# Memory-SD_UHS_II.net
KiCad netlist of a schematic drawn in Altium Designer
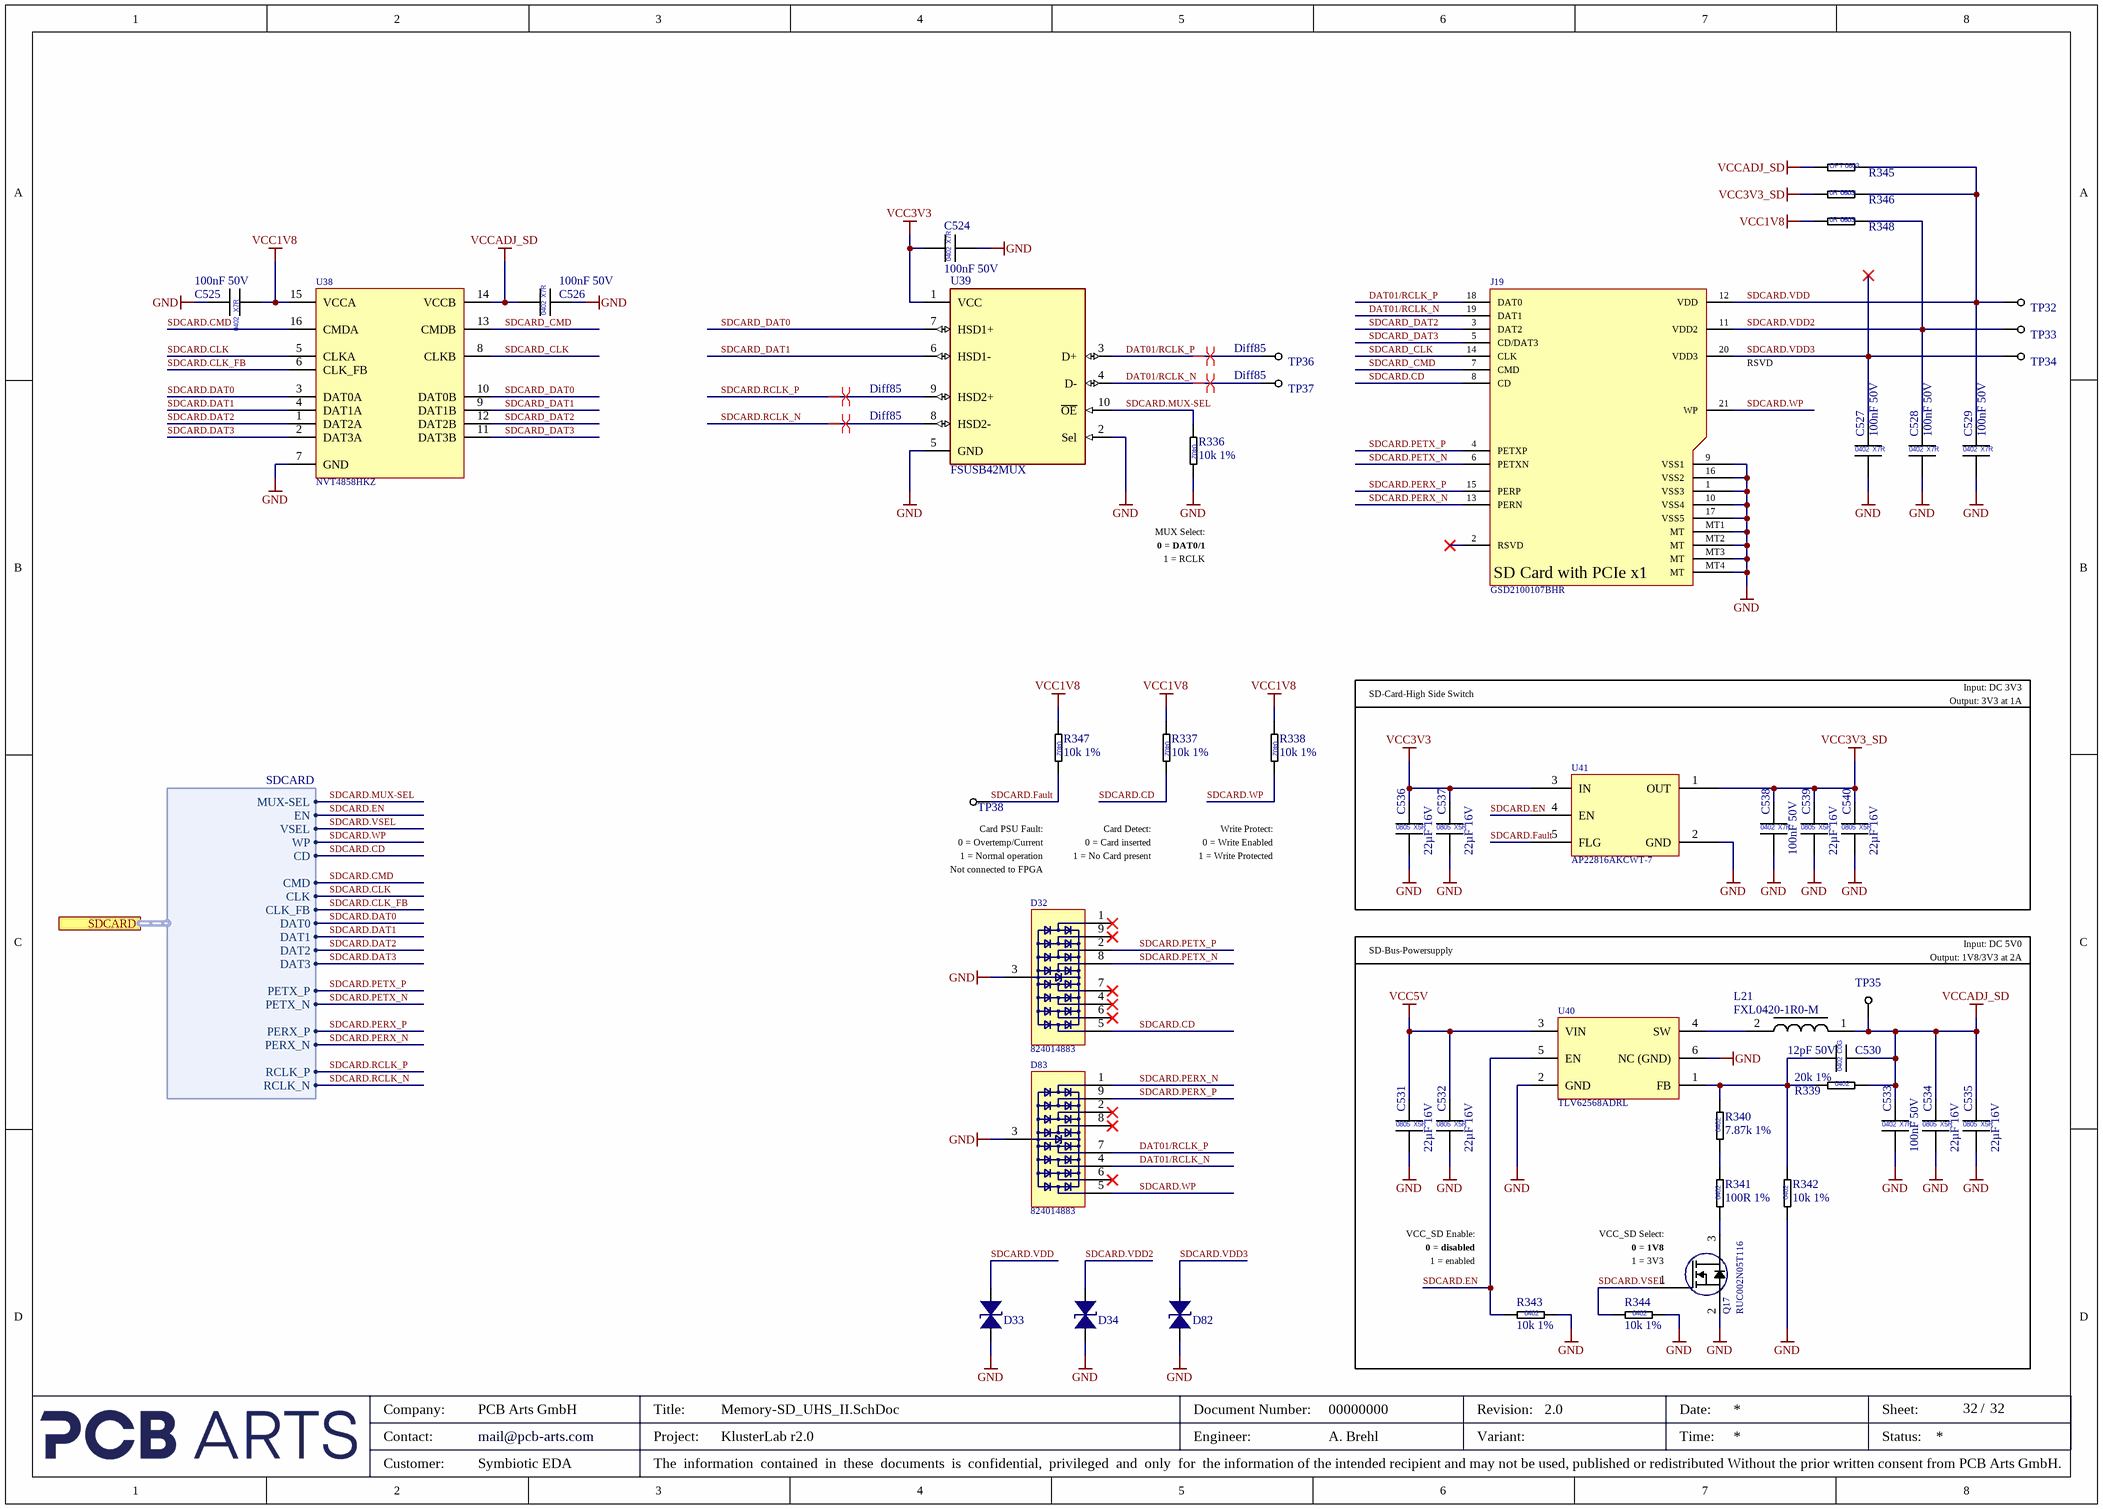
[diagram p0: Memory-SD_UHS_II.SchDoc]

(export (version "E")
  (design (tool "Eeschema 10.0.6"))
  (components
    (comp (ref "C524")
      (value "100nF 50V")
      (footprint "Cap:CAP_0402_L")
      (description "Multilayer Ceramic Capacitors MLCC - SMD/SMT 0402 50VDC")
      (libsource (lib "") (part "CAP_0402_100nF_50V_1"))
    )
    (comp (ref "C525")
      (value "100nF 50V")
      (footprint "Cap:CAP_0402_L")
      (description "Multilayer Ceramic Capacitors MLCC - SMD/SMT 0402 50VDC")
      (libsource (lib "Cap") (part "CAP_0402_100nF_50V"))
    )
    (comp (ref "C526")
      (value "100nF 50V")
      (footprint "Cap:CAP_0402_L")
      (description "Multilayer Ceramic Capacitors MLCC - SMD/SMT 0402 50VDC")
      (libsource (lib "") (part "CAP_0402_100nF_50V_1"))
    )
    (comp (ref "C527")
      (value "100nF 50V")
      (footprint "Cap:CAP_0402_L")
      (description "Multilayer Ceramic Capacitors MLCC - SMD/SMT 0402 50VDC")
      (libsource (lib "Cap") (part "CAP_0402_100nF_50V"))
    )
    (comp (ref "C528")
      (value "100nF 50V")
      (footprint "Cap:CAP_0402_L")
      (description "Multilayer Ceramic Capacitors MLCC - SMD/SMT 0402 50VDC")
      (libsource (lib "Cap") (part "CAP_0402_100nF_50V"))
    )
    (comp (ref "C529")
      (value "100nF 50V")
      (footprint "Cap:CAP_0402_L")
      (description "Multilayer Ceramic Capacitors MLCC - SMD/SMT 0402 50VDC")
      (libsource (lib "Cap") (part "CAP_0402_100nF_50V"))
    )
    (comp (ref "C530")
      (value "12pF 50V")
      (footprint "Cap:CAP_0402_L")
      (description "Multilayer Ceramic Capacitors MLCC - SMD/SMT 0402 50VDC")
      (libsource (lib "Cap") (part "CAP_0402_12pF_50V"))
    )
    (comp (ref "C531")
      (value "22µF 16V")
      (footprint "Cap:CAP_0805")
      (description "Multilayer Ceramic Capacitors MLCC - SMD/SMT 0805 16VDC")
      (libsource (lib "Cap") (part "CAP_0805_22µF_16V"))
    )
    (comp (ref "C532")
      (value "22µF 16V")
      (footprint "Cap:CAP_0805")
      (description "Multilayer Ceramic Capacitors MLCC - SMD/SMT 0805 16VDC")
      (libsource (lib "Cap") (part "CAP_0805_22µF_16V"))
    )
    (comp (ref "C533")
      (value "100nF 50V")
      (footprint "Cap:CAP_0402_L")
      (description "Multilayer Ceramic Capacitors MLCC - SMD/SMT 0402 50VDC")
      (libsource (lib "Cap") (part "CAP_0402_100nF_50V"))
    )
    (comp (ref "C534")
      (value "22µF 16V")
      (footprint "Cap:CAP_0805")
      (description "Multilayer Ceramic Capacitors MLCC - SMD/SMT 0805 16VDC")
      (libsource (lib "Cap") (part "CAP_0805_22µF_16V"))
    )
    (comp (ref "C535")
      (value "22µF 16V")
      (footprint "Cap:CAP_0805")
      (description "Multilayer Ceramic Capacitors MLCC - SMD/SMT 0805 16VDC")
      (libsource (lib "Cap") (part "CAP_0805_22µF_16V"))
    )
    (comp (ref "C536")
      (value "22µF 16V")
      (footprint "Cap:CAP_0805")
      (description "Multilayer Ceramic Capacitors MLCC - SMD/SMT 0805 16VDC")
      (libsource (lib "Cap") (part "CAP_0805_22µF_16V"))
    )
    (comp (ref "C537")
      (value "22µF 16V")
      (footprint "Cap:CAP_0805")
      (description "Multilayer Ceramic Capacitors MLCC - SMD/SMT 0805 16VDC")
      (libsource (lib "Cap") (part "CAP_0805_22µF_16V"))
    )
    (comp (ref "C538")
      (value "100nF 50V")
      (footprint "Cap:CAP_0402_L")
      (description "Multilayer Ceramic Capacitors MLCC - SMD/SMT 0402 50VDC")
      (libsource (lib "Cap") (part "CAP_0402_100nF_50V"))
    )
    (comp (ref "C539")
      (value "22µF 16V")
      (footprint "Cap:CAP_0805")
      (description "Multilayer Ceramic Capacitors MLCC - SMD/SMT 0805 16VDC")
      (libsource (lib "Cap") (part "CAP_0805_22µF_16V"))
    )
    (comp (ref "C540")
      (value "22µF 16V")
      (footprint "Cap:CAP_0805")
      (description "Multilayer Ceramic Capacitors MLCC - SMD/SMT 0805 16VDC")
      (libsource (lib "Cap") (part "CAP_0805_22µF_16V"))
    )
    (comp (ref "D32")
      (value "824014883")
      (footprint "WE-TVS-DFN3810-9L")
      (description "ESD Suppressors / TVS Diodes WE-TVS Diode Array 3.3V 0.5pF 8Channel")
      (libsource (lib "Protec") (part "824014883_ESD-Suppressors_TVS-Diodes_3.3V_0.5pF_8Chnl"))
    )
    (comp (ref "D33")
      (value "CESDP0402UC5VB")
      (footprint "Protec:TVS_0402")
      (description "Low Capacitance ESD Protection Diode 0402")
      (libsource (lib "Protec") (part "CESDP0402UC5VB_TVS Diode 0402"))
    )
    (comp (ref "D34")
      (value "CESDP0402UC5VB")
      (footprint "Protec:TVS_0402")
      (description "Low Capacitance ESD Protection Diode 0402")
      (libsource (lib "Protec") (part "CESDP0402UC5VB_TVS Diode 0402"))
    )
    (comp (ref "D82")
      (value "CESDP0402UC5VB")
      (footprint "Protec:TVS_0402")
      (description "Low Capacitance ESD Protection Diode 0402")
      (libsource (lib "Protec") (part "CESDP0402UC5VB_TVS Diode 0402"))
    )
    (comp (ref "D83")
      (value "824014883")
      (footprint "WE-TVS-DFN3810-9L")
      (description "ESD Suppressors / TVS Diodes WE-TVS Diode Array 3.3V 0.5pF 8Channel")
      (libsource (lib "Protec") (part "824014883_ESD-Suppressors_TVS-Diodes_3.3V_0.5pF_8Chnl"))
    )
    (comp (ref "J19")
      (value "Amphenol / GSD2100107BHR / SD-Card UHS-II / Side Entry / Push-Push")
      (footprint "Amphenol_GSD2100107BHR")
      (description "Horizontal SD Card UHS-II Connector with PCIe x1 Pins, Push-Push operation")
      (fields (field (name "SYMBOL TEXT") "GSD2100107BHR"))
      (libsource (lib "PCB ARTS GMBH") (part "Amphenol_GSD2100107BHR"))
    )
    (comp (ref "L21")
      (value "FXL0420-1R0-M")
      (footprint "Indc:FXL0420-1R0-M")
      (description "1uH ±20% 6A 27mΩ SMD,4.4x4.5x1.8mm Power Inductor")
      (libsource (lib "Indc") (part "1uH 6A 27mΩ  FXL0420-1R0-M"))
    )
    (comp (ref "Q17")
      (value "RUC002N05T116")
      (footprint "trans:SOT95P251X112-3N")
      (description "MOSFET N-Ch 1.2 VGS Spec")
      (libsource (lib "Trans") (part "RUC002N05T116_MOSFET N-Ch 1.2 VGS Spec"))
    )
    (comp (ref "R336")
      (value "10k 1%")
      (footprint "Res:RES_0402_L")
      (description "Thick Film Resistors - SMD 10kOhm 1%")
      (libsource (lib "Res") (part "RES_0402_10k_1%"))
    )
    (comp (ref "R337")
      (value "10k 1%")
      (footprint "Res:RES_0402_L")
      (description "Thick Film Resistors - SMD 10kOhm 1%")
      (libsource (lib "Res") (part "RES_0402_10k_1%"))
    )
    (comp (ref "R338")
      (value "10k 1%")
      (footprint "Res:RES_0402_L")
      (description "Thick Film Resistors - SMD 10kOhm 1%")
      (libsource (lib "Res") (part "RES_0402_10k_1%"))
    )
    (comp (ref "R339")
      (value "20k 1%")
      (footprint "Res:RES_0402_L")
      (description "Thick Film Resistors - SMD 20kOhm 1%")
      (libsource (lib "Res") (part "RES_0402_20k_1%"))
    )
    (comp (ref "R340")
      (value "7.87k 1%")
      (footprint "Res:RES_0402_L")
      (description "Thick Film Resistors - SMD 7.87kOhm 1%")
      (libsource (lib "Res") (part "RES_0402_7.87k_1%"))
    )
    (comp (ref "R341")
      (value "100R 1%")
      (footprint "Res:RES_0402_L")
      (description "Thick Film Resistors - SMD 100Ohm 1%")
      (libsource (lib "Res") (part "RES_0402_100R_1%"))
    )
    (comp (ref "R342")
      (value "10k 1%")
      (footprint "Res:RES_0402_L")
      (description "Thick Film Resistors - SMD 10kOhm 1%")
      (libsource (lib "Res") (part "RES_0402_10k_1%"))
    )
    (comp (ref "R343")
      (value "10k 1%")
      (footprint "Res:RES_0402_L")
      (description "Thick Film Resistors - SMD 10kOhm 1%")
      (libsource (lib "Res") (part "RES_0402_10k_1%"))
    )
    (comp (ref "R344")
      (value "10k 1%")
      (footprint "Res:RES_0402_L")
      (description "Thick Film Resistors - SMD 10kOhm 1%")
      (libsource (lib "Res") (part "RES_0402_10k_1%"))
    )
    (comp (ref "R345")
      (value "OPT")
      (footprint "Res:RES_0603_L")
      (description "Thick Film Resistors - SMD Optional")
      (libsource (lib "Res") (part "RES_0603_OPT"))
    )
    (comp (ref "R346")
      (value "0R Jumper")
      (footprint "Res:RES_0603_L")
      (description "Thick Film Resistors - SMD 0Ohm Jumper")
      (libsource (lib "Res") (part "RES_0603_0R_Jumper_1"))
    )
    (comp (ref "R347")
      (value "10k 1%")
      (footprint "Res:RES_0402_L")
      (description "Thick Film Resistors - SMD 10kOhm 1%")
      (libsource (lib "Res") (part "RES_0402_10k_1%"))
    )
    (comp (ref "R348")
      (value "0R Jumper")
      (footprint "Res:RES_0603_L")
      (description "Thick Film Resistors - SMD 0Ohm Jumper")
      (libsource (lib "Res") (part "RES_0603_0R_Jumper_1"))
    )
    (comp (ref "TP32")
      (value "Testpoint")
      (footprint "Electro_mech:Testpoint 0.8mm")
      (description "Testpoint 0.8mm")
      (libsource (lib "Electro_Mech") (part "Testpoint 0.8mm"))
    )
    (comp (ref "TP33")
      (value "Testpoint")
      (footprint "Electro_mech:Testpoint 0.8mm")
      (description "Testpoint 0.8mm")
      (libsource (lib "Electro_Mech") (part "Testpoint 0.8mm"))
    )
    (comp (ref "TP34")
      (value "Testpoint")
      (footprint "Electro_mech:Testpoint 0.8mm")
      (description "Testpoint 0.8mm")
      (libsource (lib "Electro_Mech") (part "Testpoint 0.8mm"))
    )
    (comp (ref "TP35")
      (value "Testpoint")
      (footprint "Electro_mech:Testpoint 0.8mm")
      (description "Testpoint 0.8mm")
      (libsource (lib "Electro_Mech") (part "Testpoint 0.8mm"))
    )
    (comp (ref "TP36")
      (value "Testpoint")
      (footprint "Electro_mech:Testpoint 0.8mm")
      (description "Testpoint 0.8mm")
      (libsource (lib "Electro_Mech") (part "Testpoint 0.8mm"))
    )
    (comp (ref "TP37")
      (value "Testpoint")
      (footprint "Electro_mech:Testpoint 0.8mm")
      (description "Testpoint 0.8mm")
      (libsource (lib "Electro_Mech") (part "Testpoint 0.8mm"))
    )
    (comp (ref "TP38")
      (value "Testpoint")
      (footprint "Electro_mech:Testpoint 0.8mm")
      (description "Testpoint 0.8mm")
      (libsource (lib "Electro_Mech") (part "Testpoint 0.8mm"))
    )
    (comp (ref "U38")
      (value "NVT4858HKZ")
      (footprint "Digital:QFN40P180X260X55-16N")
      (description "Levelshifter SD 3.0-SDR104, auto-direction, EMI filter and ESD protection")
      (libsource (lib "Digital") (part "NVT4858HKZ_Levelshifter SD 3.0-SDR104, auto-direction, EMI filter and ESD protection"))
    )
    (comp (ref "U39")
      (value "FSUSB42MUX")
      (footprint "digital:SOP50P300X300X110-10N")
      (description "IC USB SWITCH DPDT")
      (libsource (lib "Digital") (part "FSUSB42MUX_IC USB SWITCH DPDT"))
    )
    (comp (ref "U40")
      (value "TLV62568ADRL")
      (footprint "Power:SON50P150X80-6N")
      (description "Step Down Converter with Forced PWM in SOT563 Package")
      (libsource (lib "Power") (part "TLV62568ADRL_Step Down Converter 1A; 2A"))
    )
    (comp (ref "U41")
      (value "AP22816AKCWT-7")
      (footprint "Power:SOT95P285X140-5N")
      (description "Power Switch ICs - Power Distribution Load Switch")
      (libsource (lib "Power") (part "AP22816AKCWT-7_Power Switch ICs - Power Distribution Load Switch"))
    )
  )
  (nets
    (net (code "2") (name "/DAT01{slash}RCLK_N") (class "Default")
      (node (ref "D83") (pin "4") (pinfunction "IO3_4") (pintype "passive"))
      (node (ref "J19") (pin "19") (pinfunction "DAT1_19") (pintype "passive"))
      (node (ref "TP37") (pin "1") (pinfunction "GND_1") (pintype "passive"))
      (node (ref "U39") (pin "4") (pinfunction "D-_4") (pintype "bidirectional"))
    )
    (net (code "3") (name "/DAT01{slash}RCLK_P") (class "Default")
      (node (ref "D83") (pin "7") (pinfunction "IO6_7") (pintype "passive"))
      (node (ref "J19") (pin "18") (pinfunction "DAT0_18") (pintype "passive"))
      (node (ref "TP36") (pin "1") (pinfunction "GND_1") (pintype "passive"))
      (node (ref "U39") (pin "3") (pinfunction "D+_3") (pintype "bidirectional"))
    )
    (net (code "4") (name "/SDCARD.CD") (class "Default")
      (node (ref "D32") (pin "5") (pinfunction "IO4_5") (pintype "passive"))
      (node (ref "J19") (pin "8") (pinfunction "CD_8") (pintype "passive"))
      (node (ref "R337") (pin "2") (pinfunction "2_2") (pintype "passive"))
    )
    (net (code "5") (name "/SDCARD.CLK") (class "Default")
      (node (ref "U38") (pin "5") (pinfunction "CLKA_5") (pintype "passive"))
    )
    (net (code "6") (name "/SDCARD.CLK_FB") (class "Default")
      (node (ref "U38") (pin "6") (pinfunction "CLK_FB_6") (pintype "passive"))
    )
    (net (code "7") (name "/SDCARD.CMD") (class "Default")
      (node (ref "U38") (pin "16") (pinfunction "CMDA_16") (pintype "passive"))
    )
    (net (code "8") (name "/SDCARD.DAT0") (class "Default")
      (node (ref "U38") (pin "3") (pinfunction "DAT0A_3") (pintype "passive"))
    )
    (net (code "9") (name "/SDCARD.DAT1") (class "Default")
      (node (ref "U38") (pin "4") (pinfunction "DAT1A_4") (pintype "passive"))
    )
    (net (code "10") (name "/SDCARD.DAT2") (class "Default")
      (node (ref "U38") (pin "1") (pinfunction "DAT2A_1") (pintype "passive"))
    )
    (net (code "11") (name "/SDCARD.DAT3") (class "Default")
      (node (ref "U38") (pin "2") (pinfunction "DAT3A_2") (pintype "passive"))
    )
    (net (code "12") (name "/SDCARD.EN") (class "Default")
      (node (ref "R343") (pin "1") (pinfunction "1_1") (pintype "passive"))
      (node (ref "U40") (pin "5") (pinfunction "EN_5") (pintype "passive"))
      (node (ref "U41") (pin "4") (pinfunction "EN_4") (pintype "passive"))
    )
    (net (code "13") (name "/SDCARD.Fault") (class "Default")
      (node (ref "R347") (pin "2") (pinfunction "2_2") (pintype "passive"))
      (node (ref "TP38") (pin "1") (pinfunction "GND_1") (pintype "passive"))
      (node (ref "U41") (pin "5") (pinfunction "FLG_5") (pintype "open_collector"))
    )
    (net (code "14") (name "/SDCARD.MUX-SEL") (class "Default")
      (node (ref "R336") (pin "1") (pinfunction "1_1") (pintype "passive"))
      (node (ref "U39") (pin "10") (pinfunction "~{OE}_10") (pintype "input"))
    )
    (net (code "15") (name "/SDCARD.PERX_N") (class "Default")
      (node (ref "D83") (pin "1") (pinfunction "IO1_1") (pintype "passive"))
      (node (ref "J19") (pin "13") (pinfunction "PERN_13") (pintype "passive"))
    )
    (net (code "16") (name "/SDCARD.PERX_P") (class "Default")
      (node (ref "D83") (pin "9") (pinfunction "IO8_9") (pintype "passive"))
      (node (ref "J19") (pin "15") (pinfunction "PERP_15") (pintype "passive"))
    )
    (net (code "17") (name "/SDCARD.PETX_N") (class "Default")
      (node (ref "D32") (pin "8") (pinfunction "IO7_8") (pintype "passive"))
      (node (ref "J19") (pin "6") (pinfunction "PETXN_6") (pintype "passive"))
    )
    (net (code "18") (name "/SDCARD.PETX_P") (class "Default")
      (node (ref "D32") (pin "2") (pinfunction "IO2_2") (pintype "passive"))
      (node (ref "J19") (pin "4") (pinfunction "PETXP_4") (pintype "passive"))
    )
    (net (code "19") (name "/SDCARD.RCLK_N") (class "Default")
      (node (ref "U39") (pin "8") (pinfunction "HSD2-_8") (pintype "bidirectional"))
    )
    (net (code "20") (name "/SDCARD.RCLK_P") (class "Default")
      (node (ref "U39") (pin "9") (pinfunction "HSD2+_9") (pintype "bidirectional"))
    )
    (net (code "21") (name "/SDCARD.VDD") (class "Default")
      (node (ref "C529") (pin "1") (pinfunction "1_1") (pintype "passive"))
      (node (ref "D33") (pin "1") (pinfunction "1_1") (pintype "passive"))
      (node (ref "J19") (pin "12") (pinfunction "VDD_12") (pintype "passive"))
      (node (ref "R345") (pin "2") (pinfunction "2_2") (pintype "passive"))
      (node (ref "R346") (pin "2") (pinfunction "2_2") (pintype "passive"))
      (node (ref "TP32") (pin "1") (pinfunction "GND_1") (pintype "passive"))
    )
    (net (code "22") (name "/SDCARD.VDD2") (class "Default")
      (node (ref "C528") (pin "1") (pinfunction "1_1") (pintype "passive"))
      (node (ref "D34") (pin "1") (pinfunction "1_1") (pintype "passive"))
      (node (ref "J19") (pin "11") (pinfunction "VDD2_11") (pintype "passive"))
      (node (ref "R348") (pin "2") (pinfunction "2_2") (pintype "passive"))
      (node (ref "TP33") (pin "1") (pinfunction "GND_1") (pintype "passive"))
    )
    (net (code "23") (name "/SDCARD.VDD3") (class "Default")
      (node (ref "C527") (pin "1") (pinfunction "1_1") (pintype "passive"))
      (node (ref "D82") (pin "1") (pinfunction "1_1") (pintype "passive"))
      (node (ref "J19") (pin "20") (pinfunction "VDD3_20") (pintype "passive"))
      (node (ref "TP34") (pin "1") (pinfunction "GND_1") (pintype "passive"))
    )
    (net (code "24") (name "/SDCARD.VSEL") (class "Default")
      (node (ref "Q17") (pin "1") (pinfunction "G_1") (pintype "passive"))
      (node (ref "R344") (pin "1") (pinfunction "1_1") (pintype "passive"))
    )
    (net (code "25") (name "/SDCARD.WP") (class "Default")
      (node (ref "D83") (pin "5") (pinfunction "IO4_5") (pintype "passive"))
      (node (ref "J19") (pin "21") (pinfunction "WP_21") (pintype "passive"))
      (node (ref "R338") (pin "2") (pinfunction "2_2") (pintype "passive"))
    )
    (net (code "26") (name "/SDCARD_CLK") (class "Default")
      (node (ref "J19") (pin "14") (pinfunction "CLK_14") (pintype "passive"))
      (node (ref "U38") (pin "8") (pinfunction "CLKB_8") (pintype "passive"))
    )
    (net (code "27") (name "/SDCARD_CMD") (class "Default")
      (node (ref "J19") (pin "7") (pinfunction "CMD_7") (pintype "passive"))
      (node (ref "U38") (pin "13") (pinfunction "CMDB_13") (pintype "passive"))
    )
    (net (code "28") (name "/SDCARD_DAT0") (class "Default")
      (node (ref "U38") (pin "10") (pinfunction "DAT0B_10") (pintype "passive"))
      (node (ref "U39") (pin "7") (pinfunction "HSD1+_7") (pintype "bidirectional"))
    )
    (net (code "29") (name "/SDCARD_DAT1") (class "Default")
      (node (ref "U38") (pin "9") (pinfunction "DAT1B_9") (pintype "passive"))
      (node (ref "U39") (pin "6") (pinfunction "HSD1-_6") (pintype "bidirectional"))
    )
    (net (code "30") (name "/SDCARD_DAT2") (class "Default")
      (node (ref "J19") (pin "3") (pinfunction "DAT2_3") (pintype "passive"))
      (node (ref "U38") (pin "12") (pinfunction "DAT2B_12") (pintype "passive"))
    )
    (net (code "31") (name "/SDCARD_DAT3") (class "Default")
      (node (ref "J19") (pin "5") (pinfunction "CD/DAT3_5") (pintype "passive"))
      (node (ref "U38") (pin "11") (pinfunction "DAT3B_11") (pintype "passive"))
    )
    (net (code "33") (name "GND") (class "Default")
      (node (ref "C524") (pin "2") (pinfunction "2_2") (pintype "passive"))
      (node (ref "C525") (pin "2") (pinfunction "2_2") (pintype "passive"))
      (node (ref "C526") (pin "2") (pinfunction "2_2") (pintype "passive"))
      (node (ref "C527") (pin "2") (pinfunction "2_2") (pintype "passive"))
      (node (ref "C528") (pin "2") (pinfunction "2_2") (pintype "passive"))
      (node (ref "C529") (pin "2") (pinfunction "2_2") (pintype "passive"))
      (node (ref "C531") (pin "2") (pinfunction "2_2") (pintype "passive"))
      (node (ref "C532") (pin "2") (pinfunction "2_2") (pintype "passive"))
      (node (ref "C533") (pin "2") (pinfunction "2_2") (pintype "passive"))
      (node (ref "C534") (pin "2") (pinfunction "2_2") (pintype "passive"))
      (node (ref "C535") (pin "2") (pinfunction "2_2") (pintype "passive"))
      (node (ref "C536") (pin "2") (pinfunction "2_2") (pintype "passive"))
      (node (ref "C537") (pin "2") (pinfunction "2_2") (pintype "passive"))
      (node (ref "C538") (pin "2") (pinfunction "2_2") (pintype "passive"))
      (node (ref "C539") (pin "2") (pinfunction "2_2") (pintype "passive"))
      (node (ref "C540") (pin "2") (pinfunction "2_2") (pintype "passive"))
      (node (ref "D32") (pin "3") (pinfunction "GND_3") (pintype "passive"))
      (node (ref "D33") (pin "2") (pinfunction "2_2") (pintype "passive"))
      (node (ref "D34") (pin "2") (pinfunction "2_2") (pintype "passive"))
      (node (ref "D82") (pin "2") (pinfunction "2_2") (pintype "passive"))
      (node (ref "D83") (pin "3") (pinfunction "GND_3") (pintype "passive"))
      (node (ref "J19") (pin "1") (pinfunction "VSS3_1") (pintype "passive"))
      (node (ref "J19") (pin "10") (pinfunction "VSS4_10") (pintype "passive"))
      (node (ref "J19") (pin "16") (pinfunction "VSS2_16") (pintype "passive"))
      (node (ref "J19") (pin "17") (pinfunction "VSS5_17") (pintype "passive"))
      (node (ref "J19") (pin "9") (pinfunction "VSS1_9") (pintype "passive"))
      (node (ref "J19") (pin "MT1") (pinfunction "MT_MT1") (pintype "passive"))
      (node (ref "J19") (pin "MT2") (pinfunction "MT_MT2") (pintype "passive"))
      (node (ref "J19") (pin "MT3") (pinfunction "MT_MT3") (pintype "passive"))
      (node (ref "J19") (pin "MT4") (pinfunction "MT_MT4") (pintype "passive"))
      (node (ref "Q17") (pin "2") (pinfunction "D_2") (pintype "passive"))
      (node (ref "R336") (pin "2") (pinfunction "2_2") (pintype "passive"))
      (node (ref "R342") (pin "1") (pinfunction "1_1") (pintype "passive"))
      (node (ref "R343") (pin "2") (pinfunction "2_2") (pintype "passive"))
      (node (ref "R344") (pin "2") (pinfunction "2_2") (pintype "passive"))
      (node (ref "U38") (pin "7") (pinfunction "GND_7") (pintype "passive"))
      (node (ref "U39") (pin "2") (pinfunction "Sel_2") (pintype "input"))
      (node (ref "U39") (pin "5") (pinfunction "GND_5") (pintype "power_in"))
      (node (ref "U40") (pin "2") (pinfunction "GND_2") (pintype "passive"))
      (node (ref "U40") (pin "6") (pinfunction "NC_(GND)_6") (pintype "passive"))
      (node (ref "U41") (pin "2") (pinfunction "GND_2") (pintype "power_in"))
    )
    (net (code "34") (name "Net-(Q17-S)") (class "Default")
      (node (ref "Q17") (pin "3") (pinfunction "S_3") (pintype "passive"))
      (node (ref "R341") (pin "1") (pinfunction "1_1") (pintype "passive"))
    )
    (net (code "35") (name "Net-(R340-Pad1)") (class "Default")
      (node (ref "R340") (pin "1") (pinfunction "1_1") (pintype "passive"))
      (node (ref "R341") (pin "2") (pinfunction "2_2") (pintype "passive"))
    )
    (net (code "36") (name "Net-(U40-FB)") (class "Default")
      (node (ref "C530") (pin "1") (pinfunction "1_1") (pintype "passive"))
      (node (ref "R339") (pin "1") (pinfunction "1_1") (pintype "passive"))
      (node (ref "R340") (pin "2") (pinfunction "2_2") (pintype "passive"))
      (node (ref "R342") (pin "2") (pinfunction "2_2") (pintype "passive"))
      (node (ref "U40") (pin "1") (pinfunction "FB_1") (pintype "passive"))
    )
    (net (code "37") (name "Net-(U40-SW)") (class "Default")
      (node (ref "L21") (pin "2") (pinfunction "2_2") (pintype "passive"))
      (node (ref "U40") (pin "4") (pinfunction "SW_4") (pintype "passive"))
    )
    (net (code "38") (name "VCC1V8") (class "Default")
      (node (ref "C525") (pin "1") (pinfunction "1_1") (pintype "passive"))
      (node (ref "R337") (pin "1") (pinfunction "1_1") (pintype "passive"))
      (node (ref "R338") (pin "1") (pinfunction "1_1") (pintype "passive"))
      (node (ref "R347") (pin "1") (pinfunction "1_1") (pintype "passive"))
      (node (ref "R348") (pin "1") (pinfunction "1_1") (pintype "passive"))
      (node (ref "U38") (pin "15") (pinfunction "VCCA_15") (pintype "passive"))
    )
    (net (code "39") (name "VCC3V3") (class "Default")
      (node (ref "C524") (pin "1") (pinfunction "1_1") (pintype "passive"))
      (node (ref "C536") (pin "1") (pinfunction "1_1") (pintype "passive"))
      (node (ref "C537") (pin "1") (pinfunction "1_1") (pintype "passive"))
      (node (ref "U39") (pin "1") (pinfunction "VCC_1") (pintype "power_in"))
      (node (ref "U41") (pin "3") (pinfunction "IN_3") (pintype "power_in"))
    )
    (net (code "40") (name "VCC3V3_SD") (class "Default")
      (node (ref "C538") (pin "1") (pinfunction "1_1") (pintype "passive"))
      (node (ref "C539") (pin "1") (pinfunction "1_1") (pintype "passive"))
      (node (ref "C540") (pin "1") (pinfunction "1_1") (pintype "passive"))
      (node (ref "R346") (pin "1") (pinfunction "1_1") (pintype "passive"))
      (node (ref "U41") (pin "1") (pinfunction "OUT_1") (pintype "power_in"))
    )
    (net (code "41") (name "VCC5V") (class "Default")
      (node (ref "C531") (pin "1") (pinfunction "1_1") (pintype "passive"))
      (node (ref "C532") (pin "1") (pinfunction "1_1") (pintype "passive"))
      (node (ref "U40") (pin "3") (pinfunction "VIN_3") (pintype "passive"))
    )
    (net (code "42") (name "VCCADJ_SD") (class "Default")
      (node (ref "C526") (pin "1") (pinfunction "1_1") (pintype "passive"))
      (node (ref "C530") (pin "2") (pinfunction "2_2") (pintype "passive"))
      (node (ref "C533") (pin "1") (pinfunction "1_1") (pintype "passive"))
      (node (ref "C534") (pin "1") (pinfunction "1_1") (pintype "passive"))
      (node (ref "C535") (pin "1") (pinfunction "1_1") (pintype "passive"))
      (node (ref "L21") (pin "1") (pinfunction "1_1") (pintype "passive"))
      (node (ref "R339") (pin "2") (pinfunction "2_2") (pintype "passive"))
      (node (ref "R345") (pin "1") (pinfunction "1_1") (pintype "passive"))
      (node (ref "TP35") (pin "1") (pinfunction "GND_1") (pintype "passive"))
      (node (ref "U38") (pin "14") (pinfunction "VCCB_14") (pintype "passive"))
    )
    (net (code "43") (name "unconnected-(D32-IO1-Pad1)") (class "Default")
      (node (ref "D32") (pin "1") (pinfunction "IO1_1") (pintype "passive+no_connect"))
    )
    (net (code "44") (name "unconnected-(D32-IO3-Pad4)") (class "Default")
      (node (ref "D32") (pin "4") (pinfunction "IO3_4") (pintype "passive+no_connect"))
    )
    (net (code "45") (name "unconnected-(D32-IO5-Pad6)") (class "Default")
      (node (ref "D32") (pin "6") (pinfunction "IO5_6") (pintype "passive+no_connect"))
    )
    (net (code "46") (name "unconnected-(D32-IO6-Pad7)") (class "Default")
      (node (ref "D32") (pin "7") (pinfunction "IO6_7") (pintype "passive+no_connect"))
    )
    (net (code "47") (name "unconnected-(D32-IO8-Pad9)") (class "Default")
      (node (ref "D32") (pin "9") (pinfunction "IO8_9") (pintype "passive+no_connect"))
    )
    (net (code "48") (name "unconnected-(D83-IO2-Pad2)") (class "Default")
      (node (ref "D83") (pin "2") (pinfunction "IO2_2") (pintype "passive+no_connect"))
    )
    (net (code "49") (name "unconnected-(D83-IO5-Pad6)") (class "Default")
      (node (ref "D83") (pin "6") (pinfunction "IO5_6") (pintype "passive+no_connect"))
    )
    (net (code "50") (name "unconnected-(D83-IO7-Pad8)") (class "Default")
      (node (ref "D83") (pin "8") (pinfunction "IO7_8") (pintype "passive+no_connect"))
    )
    (net (code "51") (name "unconnected-(J19-RSVD-Pad2)") (class "Default")
      (node (ref "J19") (pin "2") (pinfunction "RSVD_2") (pintype "passive+no_connect"))
    )
  )
)
